# Sche_01.net
KiCad netlist of a schematic drawn in Altium Designer
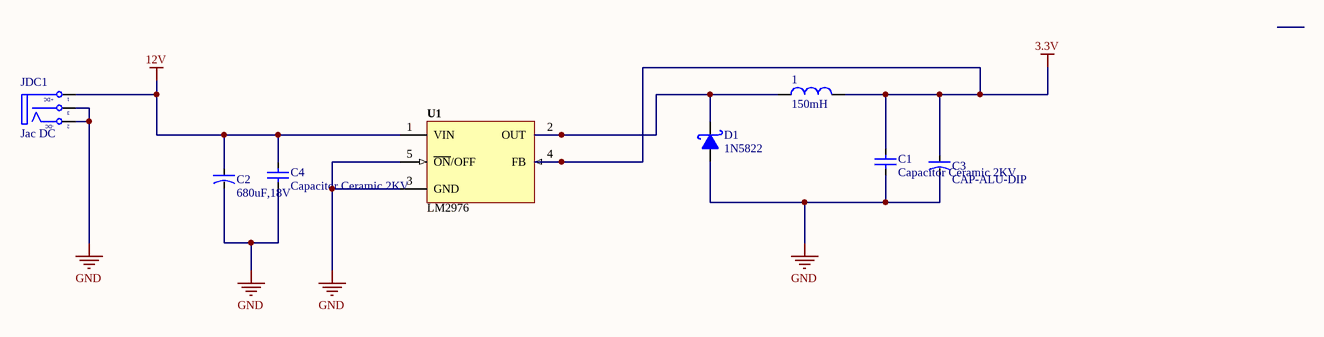
[diagram p0: Sche_01.SchDoc]

(export (version "E")
  (design (tool "Eeschema 10.0.6"))
  (components
    (comp (ref "1")
      (value "150mH")
      (footprint "L-SMD-M-7.3x4.5")
      (description "Inductor")
      (libsource (lib "My-Library") (part "Inductor"))
    )
    (comp (ref "C1")
      (value "Capacitor Ceramic 2KV")
      (footprint "CAP_0805")
      (fields (field (name "PUBLISHER") "Altium Limited"))
      (libsource (lib "My-Library") (part "Cap2KV"))
    )
    (comp (ref "C2")
      (value "680uF,18V")
      (footprint "CAP-ALU-SMD-4.5x5x1.4")
      (description "Capacitor (Semiconductor SIM Model)")
      (fields (field (name "PUBLISHER") "Altium Limited"))
      (libsource (lib "My-Library") (part "CAP-ALU-DIP"))
    )
    (comp (ref "C3")
      (value "CAP-ALU-DIP")
      (footprint "CA-ALU-2.54")
      (description "Capacitor (Semiconductor SIM Model)")
      (fields (field (name "PUBLISHER") "Altium Limited"))
      (libsource (lib "My-Library") (part "CAP-ALU-DIP"))
    )
    (comp (ref "C4")
      (value "Capacitor Ceramic 2KV")
      (footprint "CAP_0805")
      (fields (field (name "PUBLISHER") "Altium Limited"))
      (libsource (lib "My-Library") (part "Cap2KV"))
    )
    (comp (ref "D1")
      (value "1N5822")
      (footprint "SMA")
      (description "Schottky Rectifiers")
      (libsource (lib "My-Library") (part "1N5822"))
    )
    (comp (ref "JDC1")
      (value "Jac DC")
      (footprint "DC-IN")
      (description "Jac DC input")
      (libsource (lib "My-Library") (part "DCIN"))
    )
    (comp (ref "U1")
      (value "LM2976")
      (footprint "VREG_LM2596S-ADJ/NOPB")
      (libsource (lib "My-Library") (part "LM2596"))
    )
  )
  (nets
    (net (code "1") (name "3.3V") (class "Default")
      (node (ref "1") (pin "2") (pinfunction "2_2") (pintype "passive"))
      (node (ref "C1") (pin "1") (pinfunction "1_1") (pintype "passive"))
      (node (ref "C3") (pin "1") (pinfunction "1_1") (pintype "passive"))
      (node (ref "U1") (pin "4") (pinfunction "FB_4") (pintype "input"))
    )
    (net (code "2") (name "12V") (class "Default")
      (node (ref "C2") (pin "1") (pinfunction "1_1") (pintype "passive"))
      (node (ref "C4") (pin "2") (pinfunction "2_2") (pintype "passive"))
      (node (ref "JDC1") (pin "1") (pinfunction "T_1") (pintype "passive"))
      (node (ref "U1") (pin "1") (pinfunction "VIN_1") (pintype "power_in"))
    )
    (net (code "3") (name "GND") (class "Default")
      (node (ref "C1") (pin "2") (pinfunction "2_2") (pintype "passive"))
      (node (ref "C2") (pin "2") (pinfunction "2_2") (pintype "passive"))
      (node (ref "C3") (pin "2") (pinfunction "2_2") (pintype "passive"))
      (node (ref "C4") (pin "1") (pinfunction "1_1") (pintype "passive"))
      (node (ref "D1") (pin "1") (pinfunction "A_1") (pintype "passive"))
      (node (ref "JDC1") (pin "2") (pinfunction "TN_2") (pintype "passive"))
      (node (ref "JDC1") (pin "3") (pinfunction "S_3") (pintype "power_in"))
      (node (ref "U1") (pin "3") (pinfunction "GND_3") (pintype "power_in"))
      (node (ref "U1") (pin "5") (pinfunction "~{ON}/OFF_5") (pintype "input"))
    )
    (net (code "4") (name "Net-(D1-K)") (class "Default")
      (node (ref "1") (pin "1") (pinfunction "1_1") (pintype "passive"))
      (node (ref "D1") (pin "2") (pinfunction "K_2") (pintype "passive"))
      (node (ref "U1") (pin "2") (pinfunction "OUT_2") (pintype "power_in"))
    )
  )
)
